# HighPass_V_1_0.net
KiCad netlist of a schematic drawn in EAGLE
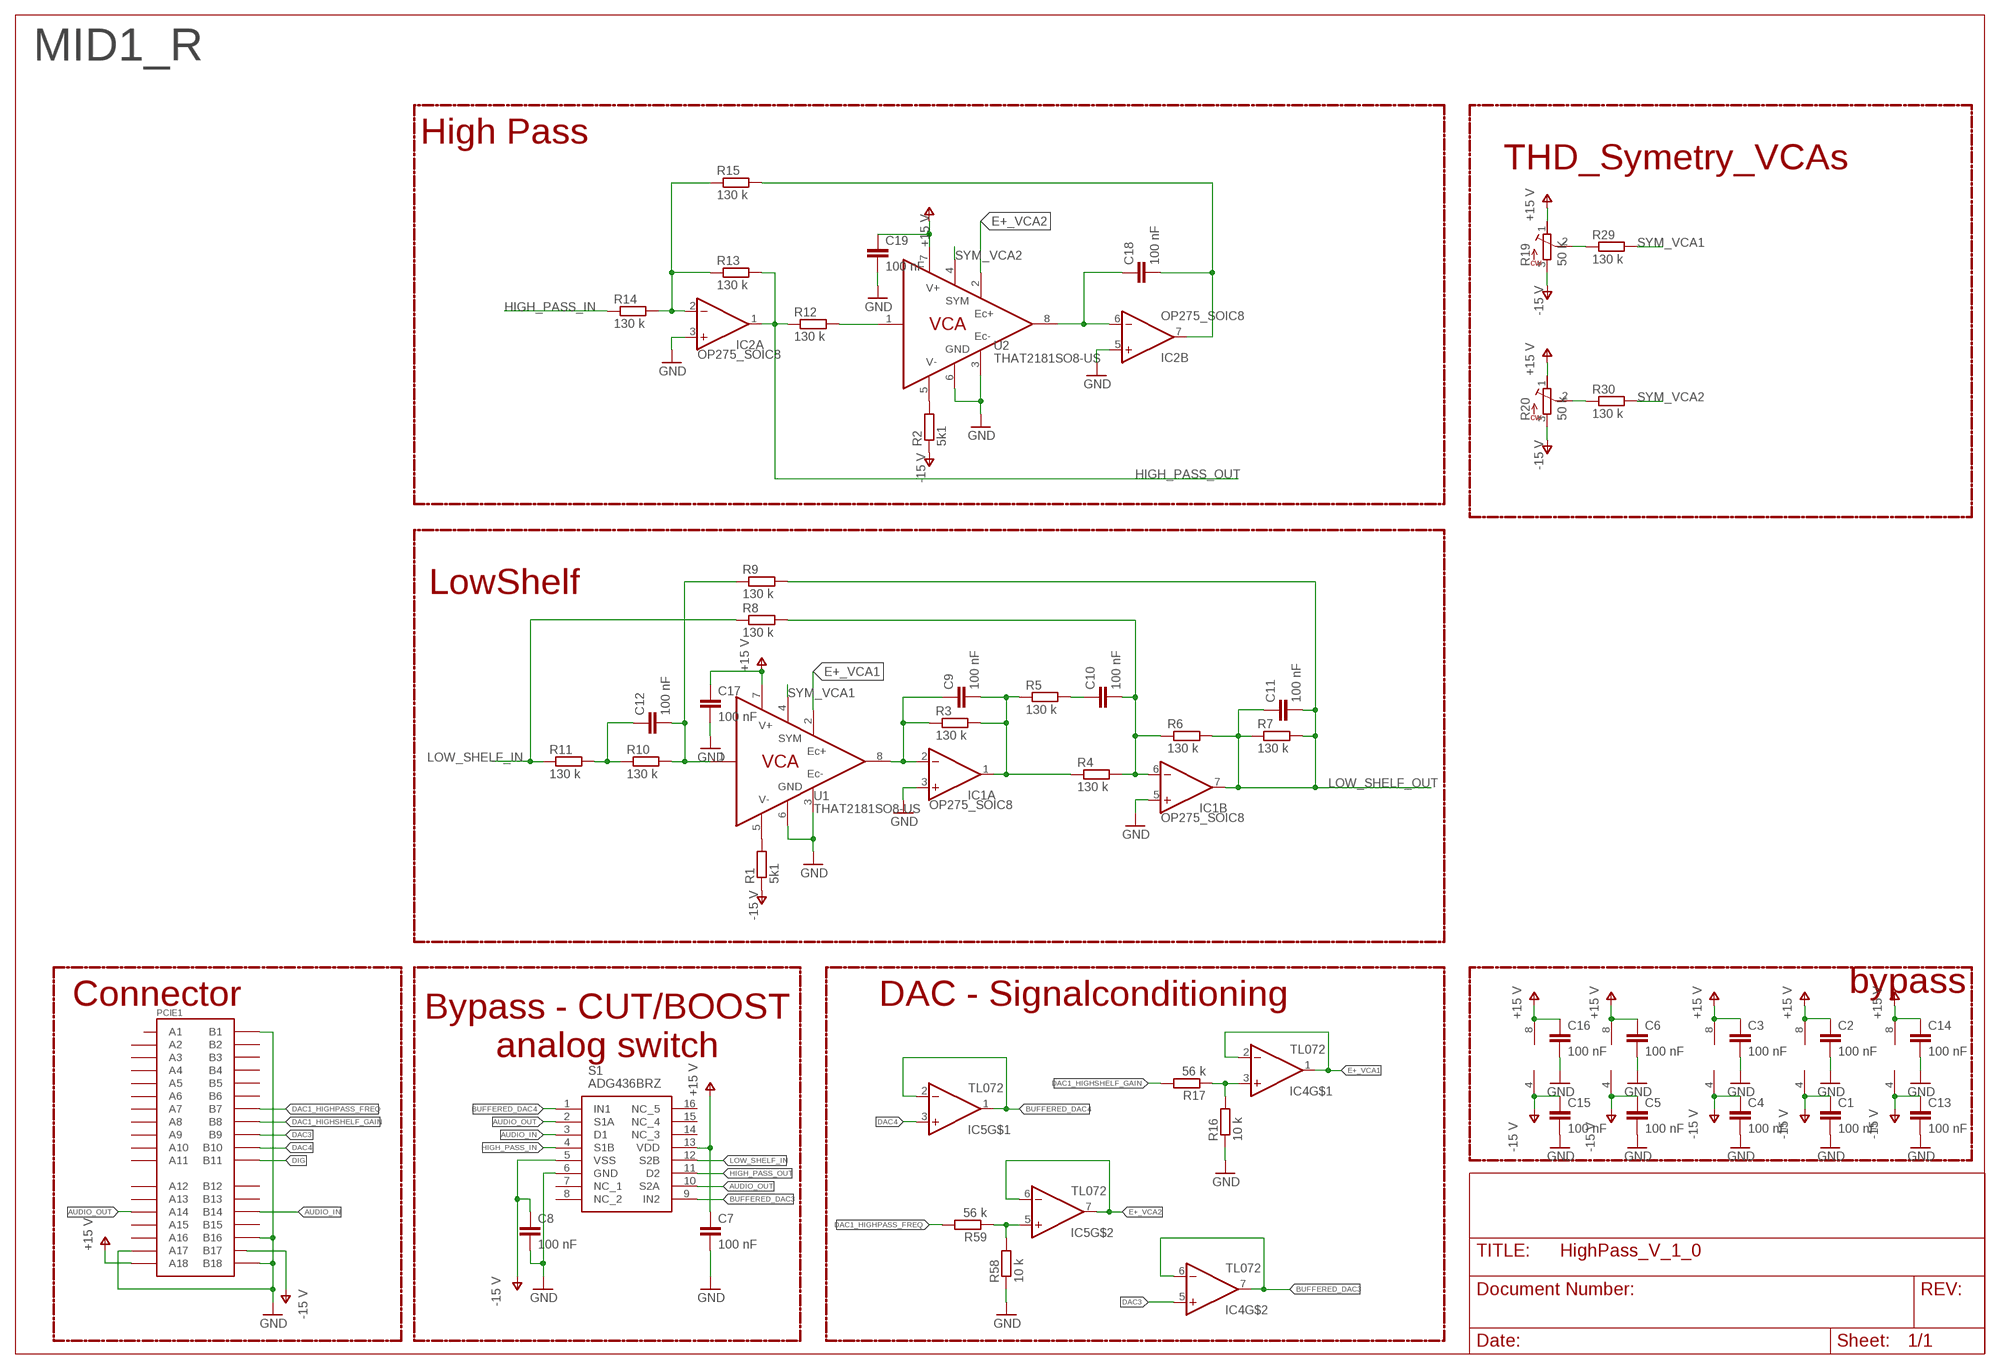
[diagram p0: schematic, sheet 1]

(export (version "E")
  (design (tool "Eeschema 10.0.6"))
  (components
    (comp (ref "C1")
      (value "100 nF")
      (footprint "eagle-import:C0603")
      (libsource (lib "eagle-import") (part "CAPACITOR_0603"))
    )
    (comp (ref "C2")
      (value "100 nF")
      (footprint "eagle-import:C0603")
      (libsource (lib "eagle-import") (part "CAPACITOR_0603"))
    )
    (comp (ref "C3")
      (value "100 nF")
      (footprint "eagle-import:C0603")
      (libsource (lib "eagle-import") (part "CAPACITOR_0603"))
    )
    (comp (ref "C4")
      (value "100 nF")
      (footprint "eagle-import:C0603")
      (libsource (lib "eagle-import") (part "CAPACITOR_0603"))
    )
    (comp (ref "C5")
      (value "100 nF")
      (footprint "eagle-import:C0603")
      (libsource (lib "eagle-import") (part "CAPACITOR_0603"))
    )
    (comp (ref "C6")
      (value "100 nF")
      (footprint "eagle-import:C0603")
      (libsource (lib "eagle-import") (part "CAPACITOR_0603"))
    )
    (comp (ref "C7")
      (value "100 nF")
      (footprint "eagle-import:C0603")
      (libsource (lib "eagle-import") (part "CAPACITOR_0603"))
    )
    (comp (ref "C8")
      (value "100 nF")
      (footprint "eagle-import:C0603")
      (libsource (lib "eagle-import") (part "CAPACITOR_0603"))
    )
    (comp (ref "C9")
      (value "100 nF")
      (footprint "eagle-import:C0603")
      (libsource (lib "eagle-import") (part "CAPACITOR_0603"))
    )
    (comp (ref "C10")
      (value "100 nF")
      (footprint "eagle-import:C0603")
      (libsource (lib "eagle-import") (part "CAPACITOR_0603"))
    )
    (comp (ref "C11")
      (value "100 nF")
      (footprint "eagle-import:C0603")
      (libsource (lib "eagle-import") (part "CAPACITOR_0603"))
    )
    (comp (ref "C12")
      (value "100 nF")
      (footprint "eagle-import:C0603")
      (libsource (lib "eagle-import") (part "CAPACITOR_0603"))
    )
    (comp (ref "C13")
      (value "100 nF")
      (footprint "eagle-import:C0603")
      (libsource (lib "eagle-import") (part "CAPACITOR_0603"))
    )
    (comp (ref "C14")
      (value "100 nF")
      (footprint "eagle-import:C0603")
      (libsource (lib "eagle-import") (part "CAPACITOR_0603"))
    )
    (comp (ref "C15")
      (value "100 nF")
      (footprint "eagle-import:C0603")
      (libsource (lib "eagle-import") (part "CAPACITOR_0603"))
    )
    (comp (ref "C16")
      (value "100 nF")
      (footprint "eagle-import:C0603")
      (libsource (lib "eagle-import") (part "CAPACITOR_0603"))
    )
    (comp (ref "C17")
      (value "100 nF")
      (footprint "eagle-import:C0603")
      (libsource (lib "eagle-import") (part "CAPACITOR_0603"))
    )
    (comp (ref "C18")
      (value "100 nF")
      (footprint "eagle-import:C0603")
      (libsource (lib "eagle-import") (part "CAPACITOR_0603"))
    )
    (comp (ref "C19")
      (value "100 nF")
      (footprint "eagle-import:C0603")
      (libsource (lib "eagle-import") (part "CAPACITOR_0603"))
    )
    (comp (ref "IC1")
      (value "OP275_SOIC8")
      (footprint "eagle-import:SOIC8")
      (fields (field (name "MOUSER_PART_NUMBER") "584-OP275GSZ-R7"))
      (libsource (lib "eagle-import") (part "OP275_SOIC8"))
    )
    (comp (ref "IC2")
      (value "OP275_SOIC8")
      (footprint "eagle-import:SOIC8")
      (fields (field (name "MOUSER_PART_NUMBER") "584-OP275GSZ-R7"))
      (libsource (lib "eagle-import") (part "OP275_SOIC8"))
    )
    (comp (ref "IC3")
      (value "OP275_SOIC8")
      (footprint "eagle-import:SOIC8")
      (fields (field (name "MOUSER_PART_NUMBER") "584-OP275GSZ-R7"))
      (libsource (lib "eagle-import") (part "OP275_SOIC8"))
    )
    (comp (ref "IC4")
      (value "TL072")
      (footprint "eagle-import:SOIC8")
      (fields (field (name "MOUSER_PART_NUMBER") "595-TL072CDR"))
      (libsource (lib "eagle-import") (part "TL072"))
    )
    (comp (ref "IC5")
      (value "TL072")
      (footprint "eagle-import:SOIC8")
      (fields (field (name "MOUSER_PART_NUMBER") "595-TL072CDR"))
      (libsource (lib "eagle-import") (part "TL072"))
    )
    (comp (ref "PCIE1")
      (value "PCIE-36-EDGE")
      (footprint "eagle-import:PCIE-36-EDGE")
      (libsource (lib "eagle-import") (part "PCIE-36-EDGE"))
    )
    (comp (ref "R1")
      (value "5k1")
      (footprint "eagle-import:R0603")
      (libsource (lib "eagle-import") (part "RESISTOR_0603"))
    )
    (comp (ref "R2")
      (value "5k1")
      (footprint "eagle-import:R0603")
      (libsource (lib "eagle-import") (part "RESISTOR_0603"))
    )
    (comp (ref "R3")
      (value "130 k")
      (footprint "eagle-import:R0603")
      (libsource (lib "eagle-import") (part "RESISTOR_0603"))
    )
    (comp (ref "R4")
      (value "130 k")
      (footprint "eagle-import:R0603")
      (libsource (lib "eagle-import") (part "RESISTOR_0603"))
    )
    (comp (ref "R5")
      (value "130 k")
      (footprint "eagle-import:R0603")
      (libsource (lib "eagle-import") (part "RESISTOR_0603"))
    )
    (comp (ref "R6")
      (value "130 k")
      (footprint "eagle-import:R0603")
      (libsource (lib "eagle-import") (part "RESISTOR_0603"))
    )
    (comp (ref "R7")
      (value "130 k")
      (footprint "eagle-import:R0603")
      (libsource (lib "eagle-import") (part "RESISTOR_0603"))
    )
    (comp (ref "R8")
      (value "130 k")
      (footprint "eagle-import:R0603")
      (libsource (lib "eagle-import") (part "RESISTOR_0603"))
    )
    (comp (ref "R9")
      (value "130 k")
      (footprint "eagle-import:R0603")
      (libsource (lib "eagle-import") (part "RESISTOR_0603"))
    )
    (comp (ref "R10")
      (value "130 k")
      (footprint "eagle-import:R0603")
      (libsource (lib "eagle-import") (part "RESISTOR_0603"))
    )
    (comp (ref "R11")
      (value "130 k")
      (footprint "eagle-import:R0603")
      (libsource (lib "eagle-import") (part "RESISTOR_0603"))
    )
    (comp (ref "R12")
      (value "130 k")
      (footprint "eagle-import:R0603")
      (libsource (lib "eagle-import") (part "RESISTOR_0603"))
    )
    (comp (ref "R13")
      (value "130 k")
      (footprint "eagle-import:R0603")
      (libsource (lib "eagle-import") (part "RESISTOR_0603"))
    )
    (comp (ref "R14")
      (value "130 k")
      (footprint "eagle-import:R0603")
      (libsource (lib "eagle-import") (part "RESISTOR_0603"))
    )
    (comp (ref "R15")
      (value "130 k")
      (footprint "eagle-import:R0603")
      (libsource (lib "eagle-import") (part "RESISTOR_0603"))
    )
    (comp (ref "R16")
      (value "10 k")
      (footprint "eagle-import:R0603")
      (libsource (lib "eagle-import") (part "RESISTOR_0603"))
    )
    (comp (ref "R17")
      (value "56 k")
      (footprint "eagle-import:R0603")
      (libsource (lib "eagle-import") (part "RESISTOR_0603"))
    )
    (comp (ref "R19")
      (value "50 K")
      (footprint "eagle-import:TC33X2503G")
      (libsource (lib "eagle-import") (part "R_TRIMMER_SMDTC33X2503G"))
    )
    (comp (ref "R20")
      (value "50 k")
      (footprint "eagle-import:TC33X2503G")
      (libsource (lib "eagle-import") (part "R_TRIMMER_SMDTC33X2503G"))
    )
    (comp (ref "R29")
      (value "130 k")
      (footprint "eagle-import:R0603")
      (libsource (lib "eagle-import") (part "RESISTOR_0603"))
    )
    (comp (ref "R30")
      (value "130 k")
      (footprint "eagle-import:R0603")
      (libsource (lib "eagle-import") (part "RESISTOR_0603"))
    )
    (comp (ref "R58")
      (value "10 k")
      (footprint "eagle-import:R0603")
      (libsource (lib "eagle-import") (part "RESISTOR_0603"))
    )
    (comp (ref "R59")
      (value "56 k")
      (footprint "eagle-import:R0603")
      (libsource (lib "eagle-import") (part "RESISTOR_0603"))
    )
    (comp (ref "S1")
      (value "ADG436BRZ")
      (footprint "eagle-import:SOIC127P600X175-16N")
      (fields (field (name "MOUSER_PART_NUMBER") "584-ADG436BRZ"))
      (libsource (lib "eagle-import") (part "ADG436BRZ"))
    )
    (comp (ref "U1")
      (value "THAT2181SO8-US")
      (footprint "eagle-import:SO08")
      (fields (field (name "MOUSER_PART_NUMBER") "887-2181CS08-U"))
      (libsource (lib "eagle-import") (part "THAT2181SSO8-U"))
    )
    (comp (ref "U2")
      (value "THAT2181SO8-US")
      (footprint "eagle-import:SO08")
      (fields (field (name "MOUSER_PART_NUMBER") "887-2181CS08-U"))
      (libsource (lib "eagle-import") (part "THAT2181SSO8-U"))
    )
  )
  (nets
    (net (code "1") (name "+15 V") (class "Default")
      (node (ref "C14") (pin "1") (pinfunction "1_1") (pintype "passive"))
      (node (ref "C16") (pin "1") (pinfunction "1_1") (pintype "passive"))
      (node (ref "C17") (pin "1") (pinfunction "1_1") (pintype "passive"))
      (node (ref "C19") (pin "1") (pinfunction "1_1") (pintype "passive"))
      (node (ref "C2") (pin "1") (pinfunction "1_1") (pintype "passive"))
      (node (ref "C3") (pin "1") (pinfunction "1_1") (pintype "passive"))
      (node (ref "C6") (pin "1") (pinfunction "1_1") (pintype "passive"))
      (node (ref "C7") (pin "1") (pinfunction "1_1") (pintype "passive"))
      (node (ref "IC1") (pin "8") (pinfunction "V+_8") (pintype "power_in"))
      (node (ref "IC2") (pin "8") (pinfunction "V+_8") (pintype "power_in"))
      (node (ref "IC3") (pin "8") (pinfunction "V+_8") (pintype "power_in"))
      (node (ref "IC4") (pin "8") (pinfunction "V+_8") (pintype "power_in"))
      (node (ref "IC5") (pin "8") (pinfunction "V+_8") (pintype "power_in"))
      (node (ref "PCIE1") (pin "A18") (pinfunction "A18_A18") (pintype "bidirectional"))
      (node (ref "R19") (pin "1") (pinfunction "3_1") (pintype "passive"))
      (node (ref "R20") (pin "1") (pinfunction "3_1") (pintype "passive"))
      (node (ref "S1") (pin "13") (pinfunction "VDD_13") (pintype "bidirectional"))
      (node (ref "U1") (pin "7") (pinfunction "V+_7") (pintype "power_in"))
      (node (ref "U2") (pin "7") (pinfunction "V+_7") (pintype "power_in"))
    )
    (net (code "2") (name "-15 V") (class "Default")
      (node (ref "C1") (pin "1") (pinfunction "1_1") (pintype "passive"))
      (node (ref "C13") (pin "1") (pinfunction "1_1") (pintype "passive"))
      (node (ref "C15") (pin "1") (pinfunction "1_1") (pintype "passive"))
      (node (ref "C4") (pin "1") (pinfunction "1_1") (pintype "passive"))
      (node (ref "C5") (pin "1") (pinfunction "1_1") (pintype "passive"))
      (node (ref "C8") (pin "1") (pinfunction "1_1") (pintype "passive"))
      (node (ref "IC1") (pin "4") (pinfunction "V-_4") (pintype "power_in"))
      (node (ref "IC2") (pin "4") (pinfunction "V-_4") (pintype "power_in"))
      (node (ref "IC3") (pin "4") (pinfunction "V-_4") (pintype "power_in"))
      (node (ref "IC4") (pin "4") (pinfunction "V-_4") (pintype "power_in"))
      (node (ref "IC5") (pin "4") (pinfunction "V-_4") (pintype "power_in"))
      (node (ref "PCIE1") (pin "B17") (pinfunction "B17_B17") (pintype "bidirectional"))
      (node (ref "R1") (pin "1") (pinfunction "1_1") (pintype "passive"))
      (node (ref "R19") (pin "3") (pinfunction "1_3") (pintype "passive"))
      (node (ref "R2") (pin "1") (pinfunction "1_1") (pintype "passive"))
      (node (ref "R20") (pin "3") (pinfunction "1_3") (pintype "passive"))
      (node (ref "S1") (pin "5") (pinfunction "VSS_5") (pintype "bidirectional"))
    )
    (net (code "3") (name "/LOW_SHELF_OUT") (class "Default")
      (node (ref "C11") (pin "1") (pinfunction "1_1") (pintype "passive"))
      (node (ref "C11") (pin "2") (pinfunction "2_2") (pintype "passive"))
      (node (ref "IC1") (pin "7") (pinfunction "OUT_7") (pintype "output"))
      (node (ref "R6") (pin "2") (pinfunction "2_2") (pintype "passive"))
      (node (ref "R7") (pin "1") (pinfunction "1_1") (pintype "passive"))
      (node (ref "R7") (pin "2") (pinfunction "2_2") (pintype "passive"))
      (node (ref "R9") (pin "2") (pinfunction "2_2") (pintype "passive"))
    )
    (net (code "4") (name "/SYM_VCA1") (class "Default")
      (node (ref "R29") (pin "2") (pinfunction "2_2") (pintype "passive"))
      (node (ref "U1") (pin "4") (pinfunction "SYM_4") (pintype "passive"))
    )
    (net (code "5") (name "/SYM_VCA2") (class "Default")
      (node (ref "R30") (pin "2") (pinfunction "2_2") (pintype "passive"))
      (node (ref "U2") (pin "4") (pinfunction "SYM_4") (pintype "passive"))
    )
    (net (code "6") (name "AUDIO_IN") (class "Default")
      (node (ref "PCIE1") (pin "B14") (pinfunction "B14_B14") (pintype "bidirectional"))
      (node (ref "S1") (pin "3") (pinfunction "D1_3") (pintype "bidirectional"))
    )
    (net (code "7") (name "AUDIO_OUT") (class "Default")
      (node (ref "PCIE1") (pin "A14") (pinfunction "A14_A14") (pintype "bidirectional"))
      (node (ref "S1") (pin "10") (pinfunction "S2A_10") (pintype "bidirectional"))
      (node (ref "S1") (pin "2") (pinfunction "S1A_2") (pintype "bidirectional"))
    )
    (net (code "8") (name "BUFFERED_DAC3") (class "Default")
      (node (ref "IC4") (pin "6") (pinfunction "-IN_6") (pintype "input"))
      (node (ref "IC4") (pin "7") (pinfunction "OUT_7") (pintype "output"))
      (node (ref "S1") (pin "9") (pinfunction "IN2_9") (pintype "bidirectional"))
    )
    (net (code "9") (name "BUFFERED_DAC4") (class "Default")
      (node (ref "IC5") (pin "1") (pinfunction "OUT_1") (pintype "output"))
      (node (ref "IC5") (pin "2") (pinfunction "-IN_2") (pintype "input"))
      (node (ref "S1") (pin "1") (pinfunction "IN1_1") (pintype "bidirectional"))
    )
    (net (code "10") (name "DAC1_HIGHPASS_FREQ") (class "Default")
      (node (ref "PCIE1") (pin "B7") (pinfunction "B7_B7") (pintype "bidirectional"))
      (node (ref "R59") (pin "2") (pinfunction "2_2") (pintype "passive"))
    )
    (net (code "11") (name "DAC1_HIGHSHELF_GAIN") (class "Default")
      (node (ref "PCIE1") (pin "B8") (pinfunction "B8_B8") (pintype "bidirectional"))
      (node (ref "R17") (pin "2") (pinfunction "2_2") (pintype "passive"))
    )
    (net (code "12") (name "DAC3") (class "Default")
      (node (ref "IC4") (pin "5") (pinfunction "+IN_5") (pintype "input"))
      (node (ref "PCIE1") (pin "B9") (pinfunction "B9_B9") (pintype "bidirectional"))
    )
    (net (code "13") (name "DAC4") (class "Default")
      (node (ref "IC5") (pin "3") (pinfunction "+IN_3") (pintype "input"))
      (node (ref "PCIE1") (pin "B10") (pinfunction "B10_B10") (pintype "bidirectional"))
    )
    (net (code "14") (name "DIG") (class "Default")
      (node (ref "PCIE1") (pin "B11") (pinfunction "B11_B11") (pintype "bidirectional"))
    )
    (net (code "15") (name "E+_VCA1") (class "Default")
      (node (ref "IC4") (pin "1") (pinfunction "OUT_1") (pintype "output"))
      (node (ref "IC4") (pin "2") (pinfunction "-IN_2") (pintype "input"))
      (node (ref "U1") (pin "2") (pinfunction "EC+_2") (pintype "passive"))
    )
    (net (code "16") (name "E+_VCA2") (class "Default")
      (node (ref "IC5") (pin "6") (pinfunction "-IN_6") (pintype "input"))
      (node (ref "IC5") (pin "7") (pinfunction "OUT_7") (pintype "output"))
      (node (ref "U2") (pin "2") (pinfunction "EC+_2") (pintype "passive"))
    )
    (net (code "17") (name "GND") (class "Default")
      (node (ref "C1") (pin "2") (pinfunction "2_2") (pintype "passive"))
      (node (ref "C13") (pin "2") (pinfunction "2_2") (pintype "passive"))
      (node (ref "C14") (pin "2") (pinfunction "2_2") (pintype "passive"))
      (node (ref "C15") (pin "2") (pinfunction "2_2") (pintype "passive"))
      (node (ref "C16") (pin "2") (pinfunction "2_2") (pintype "passive"))
      (node (ref "C17") (pin "2") (pinfunction "2_2") (pintype "passive"))
      (node (ref "C19") (pin "2") (pinfunction "2_2") (pintype "passive"))
      (node (ref "C2") (pin "2") (pinfunction "2_2") (pintype "passive"))
      (node (ref "C3") (pin "2") (pinfunction "2_2") (pintype "passive"))
      (node (ref "C4") (pin "2") (pinfunction "2_2") (pintype "passive"))
      (node (ref "C5") (pin "2") (pinfunction "2_2") (pintype "passive"))
      (node (ref "C6") (pin "2") (pinfunction "2_2") (pintype "passive"))
      (node (ref "C7") (pin "2") (pinfunction "2_2") (pintype "passive"))
      (node (ref "C8") (pin "2") (pinfunction "2_2") (pintype "passive"))
      (node (ref "IC1") (pin "3") (pinfunction "+IN_3") (pintype "input"))
      (node (ref "IC1") (pin "5") (pinfunction "+IN_5") (pintype "input"))
      (node (ref "IC2") (pin "3") (pinfunction "+IN_3") (pintype "input"))
      (node (ref "IC2") (pin "5") (pinfunction "+IN_5") (pintype "input"))
      (node (ref "PCIE1") (pin "A17") (pinfunction "A17_A17") (pintype "bidirectional"))
      (node (ref "PCIE1") (pin "B1") (pinfunction "B1_B1") (pintype "bidirectional"))
      (node (ref "PCIE1") (pin "B16") (pinfunction "B16_B16") (pintype "bidirectional"))
      (node (ref "PCIE1") (pin "B18") (pinfunction "B18_B18") (pintype "bidirectional"))
      (node (ref "R16") (pin "1") (pinfunction "1_1") (pintype "passive"))
      (node (ref "R58") (pin "1") (pinfunction "1_1") (pintype "passive"))
      (node (ref "S1") (pin "6") (pinfunction "GND_6") (pintype "bidirectional"))
      (node (ref "U1") (pin "3") (pinfunction "EC-_3") (pintype "output"))
      (node (ref "U1") (pin "6") (pinfunction "GND_6") (pintype "passive"))
      (node (ref "U2") (pin "3") (pinfunction "EC-_3") (pintype "output"))
      (node (ref "U2") (pin "6") (pinfunction "GND_6") (pintype "passive"))
    )
    (net (code "18") (name "HIGH_PASS_IN") (class "Default")
      (node (ref "R14") (pin "1") (pinfunction "1_1") (pintype "passive"))
      (node (ref "S1") (pin "4") (pinfunction "S1B_4") (pintype "bidirectional"))
    )
    (net (code "19") (name "HIGH_PASS_OUT") (class "Default")
      (node (ref "IC2") (pin "1") (pinfunction "OUT_1") (pintype "output"))
      (node (ref "R12") (pin "1") (pinfunction "1_1") (pintype "passive"))
      (node (ref "R13") (pin "2") (pinfunction "2_2") (pintype "passive"))
      (node (ref "S1") (pin "11") (pinfunction "D2_11") (pintype "bidirectional"))
    )
    (net (code "20") (name "LOW_SHELF_IN") (class "Default")
      (node (ref "R11") (pin "1") (pinfunction "1_1") (pintype "passive"))
      (node (ref "R8") (pin "1") (pinfunction "1_1") (pintype "passive"))
      (node (ref "S1") (pin "12") (pinfunction "S2B_12") (pintype "bidirectional"))
    )
    (net (code "21") (name "Net-(C10-Pad1)") (class "Default")
      (node (ref "C10") (pin "1") (pinfunction "1_1") (pintype "passive"))
      (node (ref "R5") (pin "2") (pinfunction "2_2") (pintype "passive"))
    )
    (net (code "22") (name "Net-(C12-Pad1)") (class "Default")
      (node (ref "C12") (pin "1") (pinfunction "1_1") (pintype "passive"))
      (node (ref "R10") (pin "1") (pinfunction "1_1") (pintype "passive"))
      (node (ref "R11") (pin "2") (pinfunction "2_2") (pintype "passive"))
    )
    (net (code "23") (name "Net-(IC1A--IN)") (class "Default")
      (node (ref "C9") (pin "1") (pinfunction "1_1") (pintype "passive"))
      (node (ref "IC1") (pin "2") (pinfunction "-IN_2") (pintype "input"))
      (node (ref "R3") (pin "1") (pinfunction "1_1") (pintype "passive"))
      (node (ref "U1") (pin "8") (pinfunction "OUT_8") (pintype "output"))
    )
    (net (code "24") (name "Net-(IC1A-OUT)") (class "Default")
      (node (ref "C9") (pin "2") (pinfunction "2_2") (pintype "passive"))
      (node (ref "IC1") (pin "1") (pinfunction "OUT_1") (pintype "output"))
      (node (ref "R3") (pin "2") (pinfunction "2_2") (pintype "passive"))
      (node (ref "R4") (pin "1") (pinfunction "1_1") (pintype "passive"))
      (node (ref "R5") (pin "1") (pinfunction "1_1") (pintype "passive"))
    )
    (net (code "25") (name "Net-(IC1B--IN)") (class "Default")
      (node (ref "C10") (pin "2") (pinfunction "2_2") (pintype "passive"))
      (node (ref "IC1") (pin "6") (pinfunction "-IN_6") (pintype "input"))
      (node (ref "R4") (pin "2") (pinfunction "2_2") (pintype "passive"))
      (node (ref "R6") (pin "1") (pinfunction "1_1") (pintype "passive"))
      (node (ref "R8") (pin "2") (pinfunction "2_2") (pintype "passive"))
    )
    (net (code "26") (name "Net-(IC2A--IN)") (class "Default")
      (node (ref "IC2") (pin "2") (pinfunction "-IN_2") (pintype "input"))
      (node (ref "R13") (pin "1") (pinfunction "1_1") (pintype "passive"))
      (node (ref "R14") (pin "2") (pinfunction "2_2") (pintype "passive"))
      (node (ref "R15") (pin "1") (pinfunction "1_1") (pintype "passive"))
    )
    (net (code "27") (name "Net-(IC2B--IN)") (class "Default")
      (node (ref "C18") (pin "1") (pinfunction "1_1") (pintype "passive"))
      (node (ref "IC2") (pin "6") (pinfunction "-IN_6") (pintype "input"))
      (node (ref "U2") (pin "8") (pinfunction "OUT_8") (pintype "output"))
    )
    (net (code "28") (name "Net-(IC2B-OUT)") (class "Default")
      (node (ref "C18") (pin "2") (pinfunction "2_2") (pintype "passive"))
      (node (ref "IC2") (pin "7") (pinfunction "OUT_7") (pintype "output"))
      (node (ref "R15") (pin "2") (pinfunction "2_2") (pintype "passive"))
    )
    (net (code "29") (name "Net-(IC4A-+IN)") (class "Default")
      (node (ref "IC4") (pin "3") (pinfunction "+IN_3") (pintype "input"))
      (node (ref "R16") (pin "2") (pinfunction "2_2") (pintype "passive"))
      (node (ref "R17") (pin "1") (pinfunction "1_1") (pintype "passive"))
    )
    (net (code "30") (name "Net-(IC5B-+IN)") (class "Default")
      (node (ref "IC5") (pin "5") (pinfunction "+IN_5") (pintype "input"))
      (node (ref "R58") (pin "2") (pinfunction "2_2") (pintype "passive"))
      (node (ref "R59") (pin "1") (pinfunction "1_1") (pintype "passive"))
    )
    (net (code "31") (name "Net-(R19-Pad2)") (class "Default")
      (node (ref "R19") (pin "2") (pinfunction "2_2") (pintype "passive"))
      (node (ref "R29") (pin "1") (pinfunction "1_1") (pintype "passive"))
    )
    (net (code "32") (name "Net-(R20-Pad2)") (class "Default")
      (node (ref "R20") (pin "2") (pinfunction "2_2") (pintype "passive"))
      (node (ref "R30") (pin "1") (pinfunction "1_1") (pintype "passive"))
    )
    (net (code "33") (name "Net-(U1-IN)") (class "Default")
      (node (ref "C12") (pin "2") (pinfunction "2_2") (pintype "passive"))
      (node (ref "R10") (pin "2") (pinfunction "2_2") (pintype "passive"))
      (node (ref "R9") (pin "1") (pinfunction "1_1") (pintype "passive"))
      (node (ref "U1") (pin "1") (pinfunction "IN_1") (pintype "input"))
    )
    (net (code "34") (name "Net-(U1-V-)") (class "Default")
      (node (ref "R1") (pin "2") (pinfunction "2_2") (pintype "passive"))
      (node (ref "U1") (pin "5") (pinfunction "V-_5") (pintype "power_in"))
    )
    (net (code "35") (name "Net-(U2-IN)") (class "Default")
      (node (ref "R12") (pin "2") (pinfunction "2_2") (pintype "passive"))
      (node (ref "U2") (pin "1") (pinfunction "IN_1") (pintype "input"))
    )
    (net (code "36") (name "Net-(U2-V-)") (class "Default")
      (node (ref "R2") (pin "2") (pinfunction "2_2") (pintype "passive"))
      (node (ref "U2") (pin "5") (pinfunction "V-_5") (pintype "power_in"))
    )
    (net (code "37") (name "unconnected-(PCIE1-PadA1)") (class "Default")
      (node (ref "PCIE1") (pin "A1") (pinfunction "A1_A1") (pintype "bidirectional"))
    )
    (net (code "38") (name "unconnected-(PCIE1-PadA2)") (class "Default")
      (node (ref "PCIE1") (pin "A2") (pinfunction "A2_A2") (pintype "bidirectional"))
    )
    (net (code "39") (name "unconnected-(PCIE1-PadA3)") (class "Default")
      (node (ref "PCIE1") (pin "A3") (pinfunction "A3_A3") (pintype "bidirectional"))
    )
    (net (code "40") (name "unconnected-(PCIE1-PadA4)") (class "Default")
      (node (ref "PCIE1") (pin "A4") (pinfunction "A4_A4") (pintype "bidirectional"))
    )
    (net (code "41") (name "unconnected-(PCIE1-PadA5)") (class "Default")
      (node (ref "PCIE1") (pin "A5") (pinfunction "A5_A5") (pintype "bidirectional"))
    )
    (net (code "42") (name "unconnected-(PCIE1-PadA6)") (class "Default")
      (node (ref "PCIE1") (pin "A6") (pinfunction "A6_A6") (pintype "bidirectional"))
    )
    (net (code "43") (name "unconnected-(PCIE1-PadA7)") (class "Default")
      (node (ref "PCIE1") (pin "A7") (pinfunction "A7_A7") (pintype "bidirectional"))
    )
    (net (code "44") (name "unconnected-(PCIE1-PadA8)") (class "Default")
      (node (ref "PCIE1") (pin "A8") (pinfunction "A8_A8") (pintype "bidirectional"))
    )
    (net (code "45") (name "unconnected-(PCIE1-PadA9)") (class "Default")
      (node (ref "PCIE1") (pin "A9") (pinfunction "A9_A9") (pintype "bidirectional"))
    )
    (net (code "46") (name "unconnected-(PCIE1-PadA10)") (class "Default")
      (node (ref "PCIE1") (pin "A10") (pinfunction "A10_A10") (pintype "bidirectional"))
    )
    (net (code "47") (name "unconnected-(PCIE1-PadA11)") (class "Default")
      (node (ref "PCIE1") (pin "A11") (pinfunction "A11_A11") (pintype "bidirectional"))
    )
    (net (code "48") (name "unconnected-(PCIE1-PadA12)") (class "Default")
      (node (ref "PCIE1") (pin "A12") (pinfunction "A12_A12") (pintype "bidirectional"))
    )
    (net (code "49") (name "unconnected-(PCIE1-PadA13)") (class "Default")
      (node (ref "PCIE1") (pin "A13") (pinfunction "A13_A13") (pintype "bidirectional"))
    )
    (net (code "50") (name "unconnected-(PCIE1-PadA15)") (class "Default")
      (node (ref "PCIE1") (pin "A15") (pinfunction "A15_A15") (pintype "bidirectional"))
    )
    (net (code "51") (name "unconnected-(PCIE1-PadA16)") (class "Default")
      (node (ref "PCIE1") (pin "A16") (pinfunction "A16_A16") (pintype "bidirectional"))
    )
    (net (code "52") (name "unconnected-(PCIE1-PadB2)") (class "Default")
      (node (ref "PCIE1") (pin "B2") (pinfunction "B2_B2") (pintype "bidirectional"))
    )
    (net (code "53") (name "unconnected-(PCIE1-PadB3)") (class "Default")
      (node (ref "PCIE1") (pin "B3") (pinfunction "B3_B3") (pintype "bidirectional"))
    )
    (net (code "54") (name "unconnected-(PCIE1-PadB4)") (class "Default")
      (node (ref "PCIE1") (pin "B4") (pinfunction "B4_B4") (pintype "bidirectional"))
    )
    (net (code "55") (name "unconnected-(PCIE1-PadB5)") (class "Default")
      (node (ref "PCIE1") (pin "B5") (pinfunction "B5_B5") (pintype "bidirectional"))
    )
    (net (code "56") (name "unconnected-(PCIE1-PadB6)") (class "Default")
      (node (ref "PCIE1") (pin "B6") (pinfunction "B6_B6") (pintype "bidirectional"))
    )
    (net (code "57") (name "unconnected-(PCIE1-PadB12)") (class "Default")
      (node (ref "PCIE1") (pin "B12") (pinfunction "B12_B12") (pintype "bidirectional"))
    )
    (net (code "58") (name "unconnected-(PCIE1-PadB13)") (class "Default")
      (node (ref "PCIE1") (pin "B13") (pinfunction "B13_B13") (pintype "bidirectional"))
    )
    (net (code "59") (name "unconnected-(PCIE1-PadB15)") (class "Default")
      (node (ref "PCIE1") (pin "B15") (pinfunction "B15_B15") (pintype "bidirectional"))
    )
    (net (code "60") (name "unconnected-(S1-NC_1-Pad7)") (class "Default")
      (node (ref "S1") (pin "7") (pinfunction "NC_1_7") (pintype "bidirectional"))
    )
    (net (code "61") (name "unconnected-(S1-NC_2-Pad8)") (class "Default")
      (node (ref "S1") (pin "8") (pinfunction "NC_2_8") (pintype "bidirectional"))
    )
    (net (code "62") (name "unconnected-(S1-NC_3-Pad14)") (class "Default")
      (node (ref "S1") (pin "14") (pinfunction "NC_3_14") (pintype "bidirectional"))
    )
    (net (code "63") (name "unconnected-(S1-NC_4-Pad15)") (class "Default")
      (node (ref "S1") (pin "15") (pinfunction "NC_4_15") (pintype "bidirectional"))
    )
    (net (code "64") (name "unconnected-(S1-NC_5-Pad16)") (class "Default")
      (node (ref "S1") (pin "16") (pinfunction "NC_5_16") (pintype "bidirectional"))
    )
  )
)
